# cosv-carrier-teensy40_2.net
KiCad netlist of a schematic drawn in EAGLE
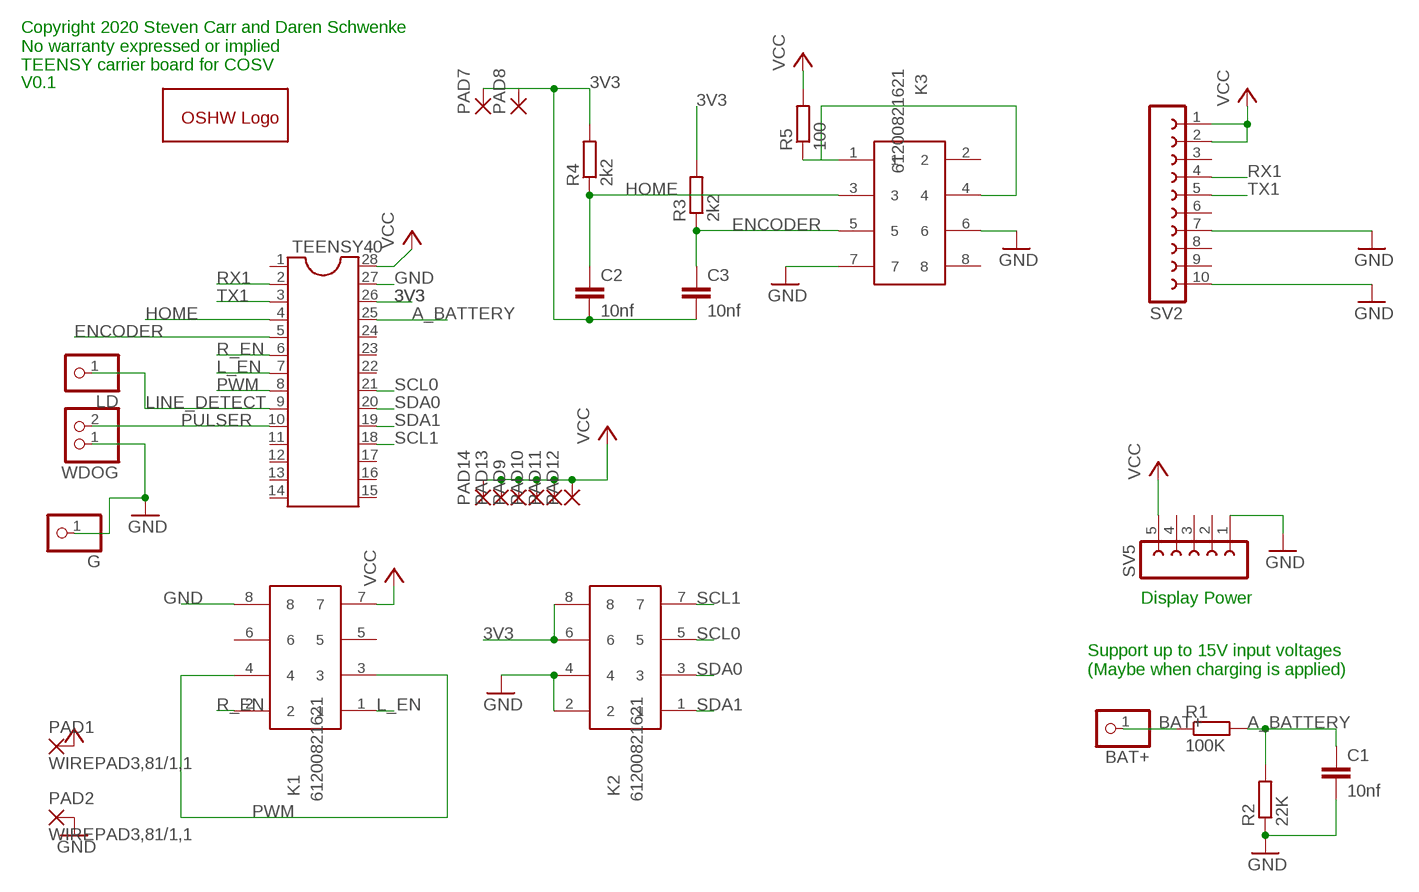
[diagram p0: schematic, sheet 1]

(export (version "E")
  (design (tool "Eeschema 10.0.6"))
  (components
    (comp (ref "BAT+")
      (value "PINHD-1X01_2.54-S")
      (footprint "eagle-import:1X01-S")
      (libsource (lib "eagle-import") (part "PINHD-1X01_2.54-S"))
    )
    (comp (ref "C1")
      (value "10nf")
      (footprint "eagle-import:C1206")
      (libsource (lib "eagle-import") (part "C-EUC1206"))
    )
    (comp (ref "C2")
      (value "10nf")
      (footprint "eagle-import:C1206")
      (libsource (lib "eagle-import") (part "C-EUC1206"))
    )
    (comp (ref "C3")
      (value "10nf")
      (footprint "eagle-import:C1206")
      (libsource (lib "eagle-import") (part "C-EUC1206"))
    )
    (comp (ref "G")
      (value "PINHD-1X01_2.54-S")
      (footprint "eagle-import:1X01-S")
      (libsource (lib "eagle-import") (part "PINHD-1X01_2.54-S"))
    )
    (comp (ref "GOLD_ORB_SM1")
      (value "OSHWLOGOLOGO8MM")
      (footprint "eagle-import:OSHW_8MM")
      (libsource (lib "eagle-import") (part "OSHWLOGOLOGO8MM"))
    )
    (comp (ref "K1")
      (value "61200821621")
      (footprint "eagle-import:61200821621")
      (libsource (lib "eagle-import") (part "61200821621"))
    )
    (comp (ref "K2")
      (value "61200821621")
      (footprint "eagle-import:61200821621")
      (libsource (lib "eagle-import") (part "61200821621"))
    )
    (comp (ref "K3")
      (value "61200821621")
      (footprint "eagle-import:61200821621")
      (libsource (lib "eagle-import") (part "61200821621"))
    )
    (comp (ref "LD")
      (value "PINHD-1X01_2.54-S")
      (footprint "eagle-import:1X01-S")
      (libsource (lib "eagle-import") (part "PINHD-1X01_2.54-S"))
    )
    (comp (ref "PAD1")
      (value "WIREPAD3,81/1,1")
      (footprint "eagle-import:3,81_1,1")
      (libsource (lib "eagle-import") (part "WIREPAD3,81/1,1"))
    )
    (comp (ref "PAD2")
      (value "WIREPAD3,81/1,1")
      (footprint "eagle-import:3,81_1,1")
      (libsource (lib "eagle-import") (part "WIREPAD3,81/1,1"))
    )
    (comp (ref "PAD7")
      (value "1,6/0,9")
      (footprint "eagle-import:1,6_0,9")
      (libsource (lib "eagle-import") (part "1,6/0,9"))
    )
    (comp (ref "PAD8")
      (value "1,6/0,9")
      (footprint "eagle-import:1,6_0,9")
      (libsource (lib "eagle-import") (part "1,6/0,9"))
    )
    (comp (ref "PAD9")
      (value "1,6/0,9")
      (footprint "eagle-import:1,6_0,9")
      (libsource (lib "eagle-import") (part "1,6/0,9"))
    )
    (comp (ref "PAD10")
      (value "1,6/0,9")
      (footprint "eagle-import:1,6_0,9")
      (libsource (lib "eagle-import") (part "1,6/0,9"))
    )
    (comp (ref "PAD11")
      (value "1,6/0,9")
      (footprint "eagle-import:1,6_0,9")
      (libsource (lib "eagle-import") (part "1,6/0,9"))
    )
    (comp (ref "PAD12")
      (value "1,6/0,9")
      (footprint "eagle-import:1,6_0,9")
      (libsource (lib "eagle-import") (part "1,6/0,9"))
    )
    (comp (ref "PAD13")
      (value "1,6/0,9")
      (footprint "eagle-import:1,6_0,9")
      (libsource (lib "eagle-import") (part "1,6/0,9"))
    )
    (comp (ref "PAD14")
      (value "1,6/0,9")
      (footprint "eagle-import:1,6_0,9")
      (libsource (lib "eagle-import") (part "1,6/0,9"))
    )
    (comp (ref "R1")
      (value "100K")
      (footprint "eagle-import:R1206")
      (libsource (lib "eagle-import") (part "R-EU_R1206"))
    )
    (comp (ref "R2")
      (value "22K")
      (footprint "eagle-import:R1206")
      (libsource (lib "eagle-import") (part "R-EU_R1206"))
    )
    (comp (ref "R3")
      (value "2k2")
      (footprint "eagle-import:R1206")
      (libsource (lib "eagle-import") (part "R-EU_R1206"))
    )
    (comp (ref "R4")
      (value "2k2")
      (footprint "eagle-import:R1206")
      (libsource (lib "eagle-import") (part "R-EU_R1206"))
    )
    (comp (ref "R5")
      (value "100")
      (footprint "eagle-import:R1206")
      (libsource (lib "eagle-import") (part "R-EU_R1206"))
    )
    (comp (ref "SV2")
      (value "FE10-1")
      (footprint "eagle-import:FE10")
      (libsource (lib "eagle-import") (part "FE10-1"))
    )
    (comp (ref "SV5")
      (value "FE05W")
      (footprint "eagle-import:FE05W")
      (libsource (lib "eagle-import") (part "FE05W"))
    )
    (comp (ref "TEENSY40")
      (value "DIL28")
      (footprint "eagle-import:DIL28-6")
      (libsource (lib "eagle-import") (part "DIL28"))
    )
    (comp (ref "WDOG")
      (value "PINHD-1X2")
      (footprint "eagle-import:1X02")
      (libsource (lib "eagle-import") (part "PINHD-1X2"))
    )
  )
  (nets
    (net (code "1") (name "/3V3") (class "Default")
      (node (ref "C2") (pin "2") (pinfunction "2_2") (pintype "passive"))
      (node (ref "C3") (pin "2") (pinfunction "2_2") (pintype "passive"))
      (node (ref "K2") (pin "6") (pinfunction "6_6") (pintype "passive"))
      (node (ref "K2") (pin "8") (pinfunction "8_8") (pintype "passive"))
      (node (ref "PAD7") (pin "1") (pinfunction "P_1") (pintype "passive"))
      (node (ref "PAD8") (pin "1") (pinfunction "P_1") (pintype "passive"))
      (node (ref "R3") (pin "2") (pinfunction "2_2") (pintype "passive"))
      (node (ref "R4") (pin "2") (pinfunction "2_2") (pintype "passive"))
      (node (ref "TEENSY40") (pin "26") (pinfunction "26_26") (pintype "passive"))
    )
    (net (code "2") (name "/A_BATTERY") (class "Default")
      (node (ref "C1") (pin "1") (pinfunction "1_1") (pintype "passive"))
      (node (ref "R1") (pin "2") (pinfunction "2_2") (pintype "passive"))
      (node (ref "R2") (pin "2") (pinfunction "2_2") (pintype "passive"))
      (node (ref "TEENSY40") (pin "25") (pinfunction "25_25") (pintype "passive"))
    )
    (net (code "3") (name "/BAT+") (class "Default")
      (node (ref "BAT+") (pin "1") (pinfunction "1_1") (pintype "passive"))
      (node (ref "R1") (pin "1") (pinfunction "1_1") (pintype "passive"))
    )
    (net (code "4") (name "/ENCODER") (class "Default")
      (node (ref "C3") (pin "1") (pinfunction "1_1") (pintype "passive"))
      (node (ref "K3") (pin "5") (pinfunction "5_5") (pintype "passive"))
      (node (ref "R3") (pin "1") (pinfunction "1_1") (pintype "passive"))
      (node (ref "TEENSY40") (pin "5") (pinfunction "5_5") (pintype "passive"))
    )
    (net (code "5") (name "/HOME") (class "Default")
      (node (ref "C2") (pin "1") (pinfunction "1_1") (pintype "passive"))
      (node (ref "K3") (pin "3") (pinfunction "3_3") (pintype "passive"))
      (node (ref "R4") (pin "1") (pinfunction "1_1") (pintype "passive"))
      (node (ref "TEENSY40") (pin "4") (pinfunction "4_4") (pintype "passive"))
    )
    (net (code "6") (name "/LINE_DETECT") (class "Default")
      (node (ref "LD") (pin "1") (pinfunction "1_1") (pintype "passive"))
      (node (ref "TEENSY40") (pin "9") (pinfunction "9_9") (pintype "passive"))
    )
    (net (code "7") (name "/L_EN") (class "Default")
      (node (ref "K1") (pin "1") (pinfunction "1_1") (pintype "passive"))
      (node (ref "TEENSY40") (pin "7") (pinfunction "7_7") (pintype "passive"))
    )
    (net (code "8") (name "/PULSER") (class "Default")
      (node (ref "TEENSY40") (pin "10") (pinfunction "10_10") (pintype "passive"))
      (node (ref "WDOG") (pin "2") (pinfunction "2_2") (pintype "passive"))
    )
    (net (code "9") (name "/PWM") (class "Default")
      (node (ref "K1") (pin "3") (pinfunction "3_3") (pintype "passive"))
      (node (ref "K1") (pin "4") (pinfunction "4_4") (pintype "passive"))
      (node (ref "TEENSY40") (pin "8") (pinfunction "8_8") (pintype "passive"))
    )
    (net (code "10") (name "/RX1") (class "Default")
      (node (ref "SV2") (pin "4") (pinfunction "4_4") (pintype "passive"))
      (node (ref "TEENSY40") (pin "2") (pinfunction "2_2") (pintype "passive"))
    )
    (net (code "11") (name "/R_EN") (class "Default")
      (node (ref "K1") (pin "2") (pinfunction "2_2") (pintype "passive"))
      (node (ref "TEENSY40") (pin "6") (pinfunction "6_6") (pintype "passive"))
    )
    (net (code "12") (name "/SCL0") (class "Default")
      (node (ref "K2") (pin "5") (pinfunction "5_5") (pintype "passive"))
      (node (ref "TEENSY40") (pin "21") (pinfunction "21_21") (pintype "passive"))
    )
    (net (code "13") (name "/SCL1") (class "Default")
      (node (ref "K2") (pin "7") (pinfunction "7_7") (pintype "passive"))
      (node (ref "TEENSY40") (pin "18") (pinfunction "18_18") (pintype "passive"))
    )
    (net (code "14") (name "/SDA0") (class "Default")
      (node (ref "K2") (pin "3") (pinfunction "3_3") (pintype "passive"))
      (node (ref "TEENSY40") (pin "20") (pinfunction "20_20") (pintype "passive"))
    )
    (net (code "15") (name "/SDA1") (class "Default")
      (node (ref "K2") (pin "1") (pinfunction "1_1") (pintype "passive"))
      (node (ref "TEENSY40") (pin "19") (pinfunction "19_19") (pintype "passive"))
    )
    (net (code "16") (name "/TX1") (class "Default")
      (node (ref "SV2") (pin "5") (pinfunction "5_5") (pintype "passive"))
      (node (ref "TEENSY40") (pin "3") (pinfunction "3_3") (pintype "passive"))
    )
    (net (code "17") (name "GND") (class "Default")
      (node (ref "C1") (pin "2") (pinfunction "2_2") (pintype "passive"))
      (node (ref "G") (pin "1") (pinfunction "1_1") (pintype "passive"))
      (node (ref "K1") (pin "8") (pinfunction "8_8") (pintype "passive"))
      (node (ref "K2") (pin "2") (pinfunction "2_2") (pintype "passive"))
      (node (ref "K2") (pin "4") (pinfunction "4_4") (pintype "passive"))
      (node (ref "K3") (pin "6") (pinfunction "6_6") (pintype "passive"))
      (node (ref "K3") (pin "7") (pinfunction "7_7") (pintype "passive"))
      (node (ref "PAD2") (pin "1") (pinfunction "P_1") (pintype "passive"))
      (node (ref "R2") (pin "1") (pinfunction "1_1") (pintype "passive"))
      (node (ref "SV2") (pin "10") (pinfunction "10_10") (pintype "passive"))
      (node (ref "SV2") (pin "7") (pinfunction "7_7") (pintype "passive"))
      (node (ref "SV5") (pin "1") (pinfunction "1_1") (pintype "passive"))
      (node (ref "TEENSY40") (pin "27") (pinfunction "27_27") (pintype "passive"))
      (node (ref "WDOG") (pin "1") (pinfunction "1_1") (pintype "passive"))
    )
    (net (code "18") (name "Net-(K3-Pad1)") (class "Default")
      (node (ref "K3") (pin "1") (pinfunction "1_1") (pintype "passive"))
      (node (ref "K3") (pin "4") (pinfunction "4_4") (pintype "passive"))
      (node (ref "R5") (pin "1") (pinfunction "1_1") (pintype "passive"))
    )
    (net (code "19") (name "VCC") (class "Default")
      (node (ref "K1") (pin "7") (pinfunction "7_7") (pintype "passive"))
      (node (ref "PAD1") (pin "1") (pinfunction "P_1") (pintype "passive"))
      (node (ref "PAD10") (pin "1") (pinfunction "P_1") (pintype "passive"))
      (node (ref "PAD11") (pin "1") (pinfunction "P_1") (pintype "passive"))
      (node (ref "PAD12") (pin "1") (pinfunction "P_1") (pintype "passive"))
      (node (ref "PAD13") (pin "1") (pinfunction "P_1") (pintype "passive"))
      (node (ref "PAD14") (pin "1") (pinfunction "P_1") (pintype "passive"))
      (node (ref "PAD9") (pin "1") (pinfunction "P_1") (pintype "passive"))
      (node (ref "R5") (pin "2") (pinfunction "2_2") (pintype "passive"))
      (node (ref "SV2") (pin "1") (pinfunction "1_1") (pintype "passive"))
      (node (ref "SV2") (pin "2") (pinfunction "2_2") (pintype "passive"))
      (node (ref "SV5") (pin "5") (pinfunction "5_5") (pintype "passive"))
      (node (ref "TEENSY40") (pin "28") (pinfunction "28_28") (pintype "passive"))
    )
    (net (code "20") (name "unconnected-(K1-Pad5)") (class "Default")
      (node (ref "K1") (pin "5") (pinfunction "5_5") (pintype "passive"))
    )
    (net (code "21") (name "unconnected-(K1-Pad6)") (class "Default")
      (node (ref "K1") (pin "6") (pinfunction "6_6") (pintype "passive"))
    )
    (net (code "22") (name "unconnected-(K3-Pad2)") (class "Default")
      (node (ref "K3") (pin "2") (pinfunction "2_2") (pintype "passive"))
    )
    (net (code "23") (name "unconnected-(K3-Pad8)") (class "Default")
      (node (ref "K3") (pin "8") (pinfunction "8_8") (pintype "passive"))
    )
    (net (code "24") (name "unconnected-(SV2-Pad3)") (class "Default")
      (node (ref "SV2") (pin "3") (pinfunction "3_3") (pintype "passive"))
    )
    (net (code "25") (name "unconnected-(SV2-Pad6)") (class "Default")
      (node (ref "SV2") (pin "6") (pinfunction "6_6") (pintype "passive"))
    )
    (net (code "26") (name "unconnected-(SV2-Pad8)") (class "Default")
      (node (ref "SV2") (pin "8") (pinfunction "8_8") (pintype "passive"))
    )
    (net (code "27") (name "unconnected-(SV2-Pad9)") (class "Default")
      (node (ref "SV2") (pin "9") (pinfunction "9_9") (pintype "passive"))
    )
    (net (code "28") (name "unconnected-(SV5-Pad2)") (class "Default")
      (node (ref "SV5") (pin "2") (pinfunction "2_2") (pintype "passive"))
    )
    (net (code "29") (name "unconnected-(SV5-Pad3)") (class "Default")
      (node (ref "SV5") (pin "3") (pinfunction "3_3") (pintype "passive"))
    )
    (net (code "30") (name "unconnected-(SV5-Pad4)") (class "Default")
      (node (ref "SV5") (pin "4") (pinfunction "4_4") (pintype "passive"))
    )
    (net (code "31") (name "unconnected-(TEENSY40-Pad1)") (class "Default")
      (node (ref "TEENSY40") (pin "1") (pinfunction "1_1") (pintype "passive"))
    )
    (net (code "32") (name "unconnected-(TEENSY40-Pad11)") (class "Default")
      (node (ref "TEENSY40") (pin "11") (pinfunction "11_11") (pintype "passive"))
    )
    (net (code "33") (name "unconnected-(TEENSY40-Pad12)") (class "Default")
      (node (ref "TEENSY40") (pin "12") (pinfunction "12_12") (pintype "passive"))
    )
    (net (code "34") (name "unconnected-(TEENSY40-Pad13)") (class "Default")
      (node (ref "TEENSY40") (pin "13") (pinfunction "13_13") (pintype "passive"))
    )
    (net (code "35") (name "unconnected-(TEENSY40-Pad14)") (class "Default")
      (node (ref "TEENSY40") (pin "14") (pinfunction "14_14") (pintype "passive"))
    )
    (net (code "36") (name "unconnected-(TEENSY40-Pad15)") (class "Default")
      (node (ref "TEENSY40") (pin "15") (pinfunction "15_15") (pintype "passive"))
    )
    (net (code "37") (name "unconnected-(TEENSY40-Pad16)") (class "Default")
      (node (ref "TEENSY40") (pin "16") (pinfunction "16_16") (pintype "passive"))
    )
    (net (code "38") (name "unconnected-(TEENSY40-Pad17)") (class "Default")
      (node (ref "TEENSY40") (pin "17") (pinfunction "17_17") (pintype "passive"))
    )
    (net (code "39") (name "unconnected-(TEENSY40-Pad22)") (class "Default")
      (node (ref "TEENSY40") (pin "22") (pinfunction "22_22") (pintype "passive"))
    )
    (net (code "40") (name "unconnected-(TEENSY40-Pad23)") (class "Default")
      (node (ref "TEENSY40") (pin "23") (pinfunction "23_23") (pintype "passive"))
    )
    (net (code "41") (name "unconnected-(TEENSY40-Pad24)") (class "Default")
      (node (ref "TEENSY40") (pin "24") (pinfunction "24_24") (pintype "passive"))
    )
  )
)
